# dragonite2.net
KiCad netlist of a schematic drawn in EAGLE
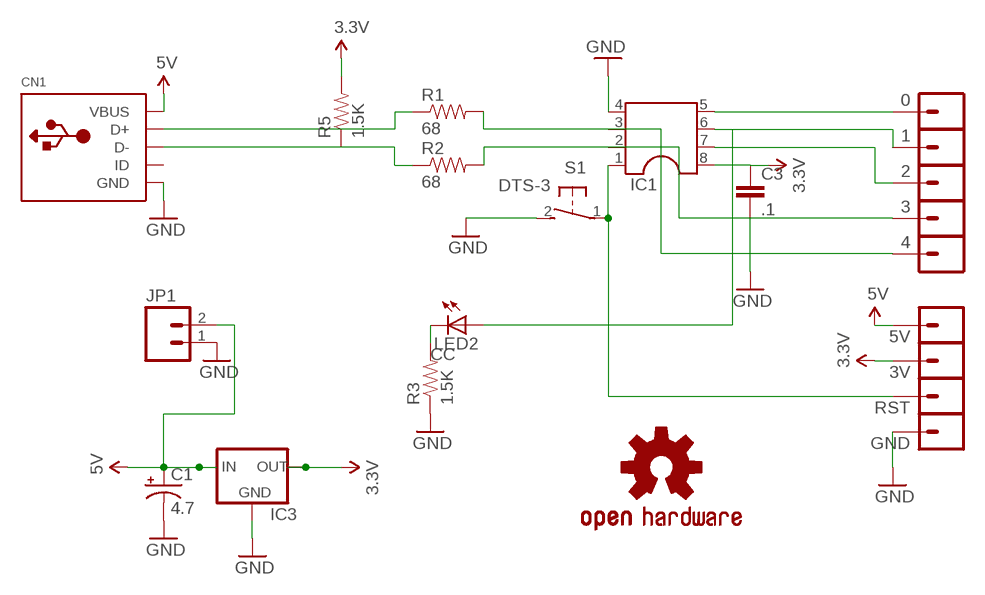
[diagram p0: schematic, sheet 1]

(export (version "E")
  (design (tool "Eeschema 10.0.6"))
  (components
    (comp (ref "0")
      (value "M01SMDNS")
      (footprint "eagle-import:1X01NS")
      (libsource (lib "eagle-import") (part "M01SMDNS"))
    )
    (comp (ref "1")
      (value "M01SMDNS")
      (footprint "eagle-import:1X01NS")
      (libsource (lib "eagle-import") (part "M01SMDNS"))
    )
    (comp (ref "2")
      (value "M01SMDNS")
      (footprint "eagle-import:1X01NS")
      (libsource (lib "eagle-import") (part "M01SMDNS"))
    )
    (comp (ref "3")
      (value "M01SMDNS")
      (footprint "eagle-import:1X01NS")
      (libsource (lib "eagle-import") (part "M01SMDNS"))
    )
    (comp (ref "3V")
      (value "M01SMDNS")
      (footprint "eagle-import:1X01NS")
      (libsource (lib "eagle-import") (part "M01SMDNS"))
    )
    (comp (ref "4")
      (value "M01SMDNS")
      (footprint "eagle-import:1X01NS")
      (libsource (lib "eagle-import") (part "M01SMDNS"))
    )
    (comp (ref "5V")
      (value "M01SMDNS")
      (footprint "eagle-import:1X01NS")
      (libsource (lib "eagle-import") (part "M01SMDNS"))
    )
    (comp (ref "C1")
      (value "4.7")
      (footprint "eagle-import:E2-4")
      (libsource (lib "eagle-import") (part "CPOL-USE2-4"))
    )
    (comp (ref "C3")
      (value ".1")
      (footprint "eagle-import:CAP-PTH-SMALLEZ")
      (libsource (lib "eagle-import") (part "CAPEZ"))
    )
    (comp (ref "CN1")
      (value "USBMOLEX")
      (footprint "eagle-import:USB-MINIB-THM-MOLEX")
      (libsource (lib "eagle-import") (part "USBMOLEX"))
    )
    (comp (ref "GND")
      (value "M01SMDNS")
      (footprint "eagle-import:1X01NS")
      (libsource (lib "eagle-import") (part "M01SMDNS"))
    )
    (comp (ref "IC1")
      (value "DIL8")
      (footprint "eagle-import:DIL08")
      (libsource (lib "eagle-import") (part "DIL8"))
    )
    (comp (ref "IC3")
      (value "V_REG_78XXTO-92")
      (footprint "eagle-import:TO-92")
      (libsource (lib "eagle-import") (part "V_REG_78XXTO-92"))
    )
    (comp (ref "JP1")
      (value "M02JST-PTH-2")
      (footprint "eagle-import:JST-2-PTH")
      (libsource (lib "eagle-import") (part "M02JST-PTH-2"))
    )
    (comp (ref "LED2")
      (value "LED3MM")
      (footprint "eagle-import:LED3MM")
      (libsource (lib "eagle-import") (part "LED3MM"))
    )
    (comp (ref "R1")
      (value "68")
      (footprint "eagle-import:1_6W-RES")
      (libsource (lib "eagle-import") (part "RESISTORPTH-1/6W"))
    )
    (comp (ref "R2")
      (value "68")
      (footprint "eagle-import:1_6W-RES")
      (libsource (lib "eagle-import") (part "RESISTORPTH-1/6W"))
    )
    (comp (ref "R3")
      (value "1.5K")
      (footprint "eagle-import:1_6W-RES")
      (libsource (lib "eagle-import") (part "RESISTORPTH-1/6W"))
    )
    (comp (ref "R5")
      (value "1.5K")
      (footprint "eagle-import:1_6W-RES")
      (libsource (lib "eagle-import") (part "RESISTORPTH-1/6W"))
    )
    (comp (ref "RST")
      (value "M01SMDNS")
      (footprint "eagle-import:1X01NS")
      (libsource (lib "eagle-import") (part "M01SMDNS"))
    )
    (comp (ref "S1")
      (value "DTS-3")
      (footprint "eagle-import:DTS-3")
      (libsource (lib "eagle-import") (part "DTS-3"))
    )
    (comp (ref "U$4")
      (value "OSHW-LOGOS")
      (footprint "eagle-import:OSHW-LOGO-S")
      (libsource (lib "eagle-import") (part "OSHW-LOGOS"))
    )
  )
  (nets
    (net (code "1") (name "3.3V") (class "Default")
      (node (ref "3V") (pin "1") (pinfunction "1_1") (pintype "passive"))
      (node (ref "C3") (pin "1") (pinfunction "1_1") (pintype "passive"))
      (node (ref "IC1") (pin "8") (pinfunction "8_8") (pintype "passive"))
      (node (ref "IC3") (pin "3") (pinfunction "OUT_3") (pintype "power_in"))
      (node (ref "R5") (pin "2") (pinfunction "2_2") (pintype "passive"))
    )
    (net (code "2") (name "5V") (class "Default")
      (node (ref "5V") (pin "1") (pinfunction "1_1") (pintype "passive"))
      (node (ref "C1") (pin "+") (pinfunction "+_+") (pintype "passive"))
      (node (ref "CN1") (pin "VBUS") (pinfunction "VBUS_VBUS") (pintype "power_in"))
      (node (ref "IC3") (pin "2") (pinfunction "IN_2") (pintype "input"))
      (node (ref "JP1") (pin "2") (pinfunction "2_2") (pintype "passive"))
    )
    (net (code "3") (name "GND") (class "Default")
      (node (ref "C1") (pin "-") (pinfunction "-_-") (pintype "passive"))
      (node (ref "C3") (pin "2") (pinfunction "2_2") (pintype "passive"))
      (node (ref "CN1") (pin "GND") (pinfunction "GND_GND") (pintype "power_in"))
      (node (ref "GND") (pin "1") (pinfunction "1_1") (pintype "passive"))
      (node (ref "IC1") (pin "4") (pinfunction "4_4") (pintype "passive"))
      (node (ref "IC3") (pin "1") (pinfunction "GND_1") (pintype "power_in"))
      (node (ref "JP1") (pin "1") (pinfunction "1_1") (pintype "passive"))
      (node (ref "R3") (pin "1") (pinfunction "1_1") (pintype "passive"))
      (node (ref "S1") (pin "2") (pinfunction "2_2") (pintype "passive"))
    )
    (net (code "4") (name "Net-(0-Pad1)") (class "Default")
      (node (ref "0") (pin "1") (pinfunction "1_1") (pintype "passive"))
      (node (ref "IC1") (pin "5") (pinfunction "5_5") (pintype "passive"))
    )
    (net (code "5") (name "Net-(1-Pad1)") (class "Default")
      (node (ref "1") (pin "1") (pinfunction "1_1") (pintype "passive"))
      (node (ref "IC1") (pin "6") (pinfunction "6_6") (pintype "passive"))
      (node (ref "LED2") (pin "A") (pinfunction "A_A") (pintype "passive"))
    )
    (net (code "6") (name "Net-(2-Pad1)") (class "Default")
      (node (ref "2") (pin "1") (pinfunction "1_1") (pintype "passive"))
      (node (ref "IC1") (pin "7") (pinfunction "7_7") (pintype "passive"))
    )
    (net (code "7") (name "Net-(3-Pad1)") (class "Default")
      (node (ref "3") (pin "1") (pinfunction "1_1") (pintype "passive"))
      (node (ref "IC1") (pin "2") (pinfunction "2_2") (pintype "passive"))
      (node (ref "R2") (pin "2") (pinfunction "2_2") (pintype "passive"))
    )
    (net (code "8") (name "Net-(4-Pad1)") (class "Default")
      (node (ref "4") (pin "1") (pinfunction "1_1") (pintype "passive"))
      (node (ref "IC1") (pin "3") (pinfunction "3_3") (pintype "passive"))
      (node (ref "R1") (pin "2") (pinfunction "2_2") (pintype "passive"))
    )
    (net (code "9") (name "Net-(CN1-PadD+)") (class "Default")
      (node (ref "CN1") (pin "D+") (pinfunction "D+_D+") (pintype "bidirectional"))
      (node (ref "R1") (pin "1") (pinfunction "1_1") (pintype "passive"))
    )
    (net (code "10") (name "Net-(CN1-PadD-)") (class "Default")
      (node (ref "CN1") (pin "D-") (pinfunction "D-_D-") (pintype "bidirectional"))
      (node (ref "R2") (pin "1") (pinfunction "1_1") (pintype "passive"))
      (node (ref "R5") (pin "1") (pinfunction "1_1") (pintype "passive"))
    )
    (net (code "11") (name "Net-(IC1-Pad1)") (class "Default")
      (node (ref "IC1") (pin "1") (pinfunction "1_1") (pintype "passive"))
      (node (ref "RST") (pin "1") (pinfunction "1_1") (pintype "passive"))
      (node (ref "S1") (pin "1") (pinfunction "1_1") (pintype "passive"))
    )
    (net (code "12") (name "Net-(LED2-C)") (class "Default")
      (node (ref "LED2") (pin "K") (pinfunction "C_K") (pintype "passive"))
      (node (ref "R3") (pin "2") (pinfunction "2_2") (pintype "passive"))
    )
    (net (code "13") (name "unconnected-(CN1-PadID)") (class "Default")
      (node (ref "CN1") (pin "ID") (pinfunction "ID_ID") (pintype "bidirectional"))
    )
  )
)
